# 1bl.net
KiCad netlist of a schematic drawn in EAGLE
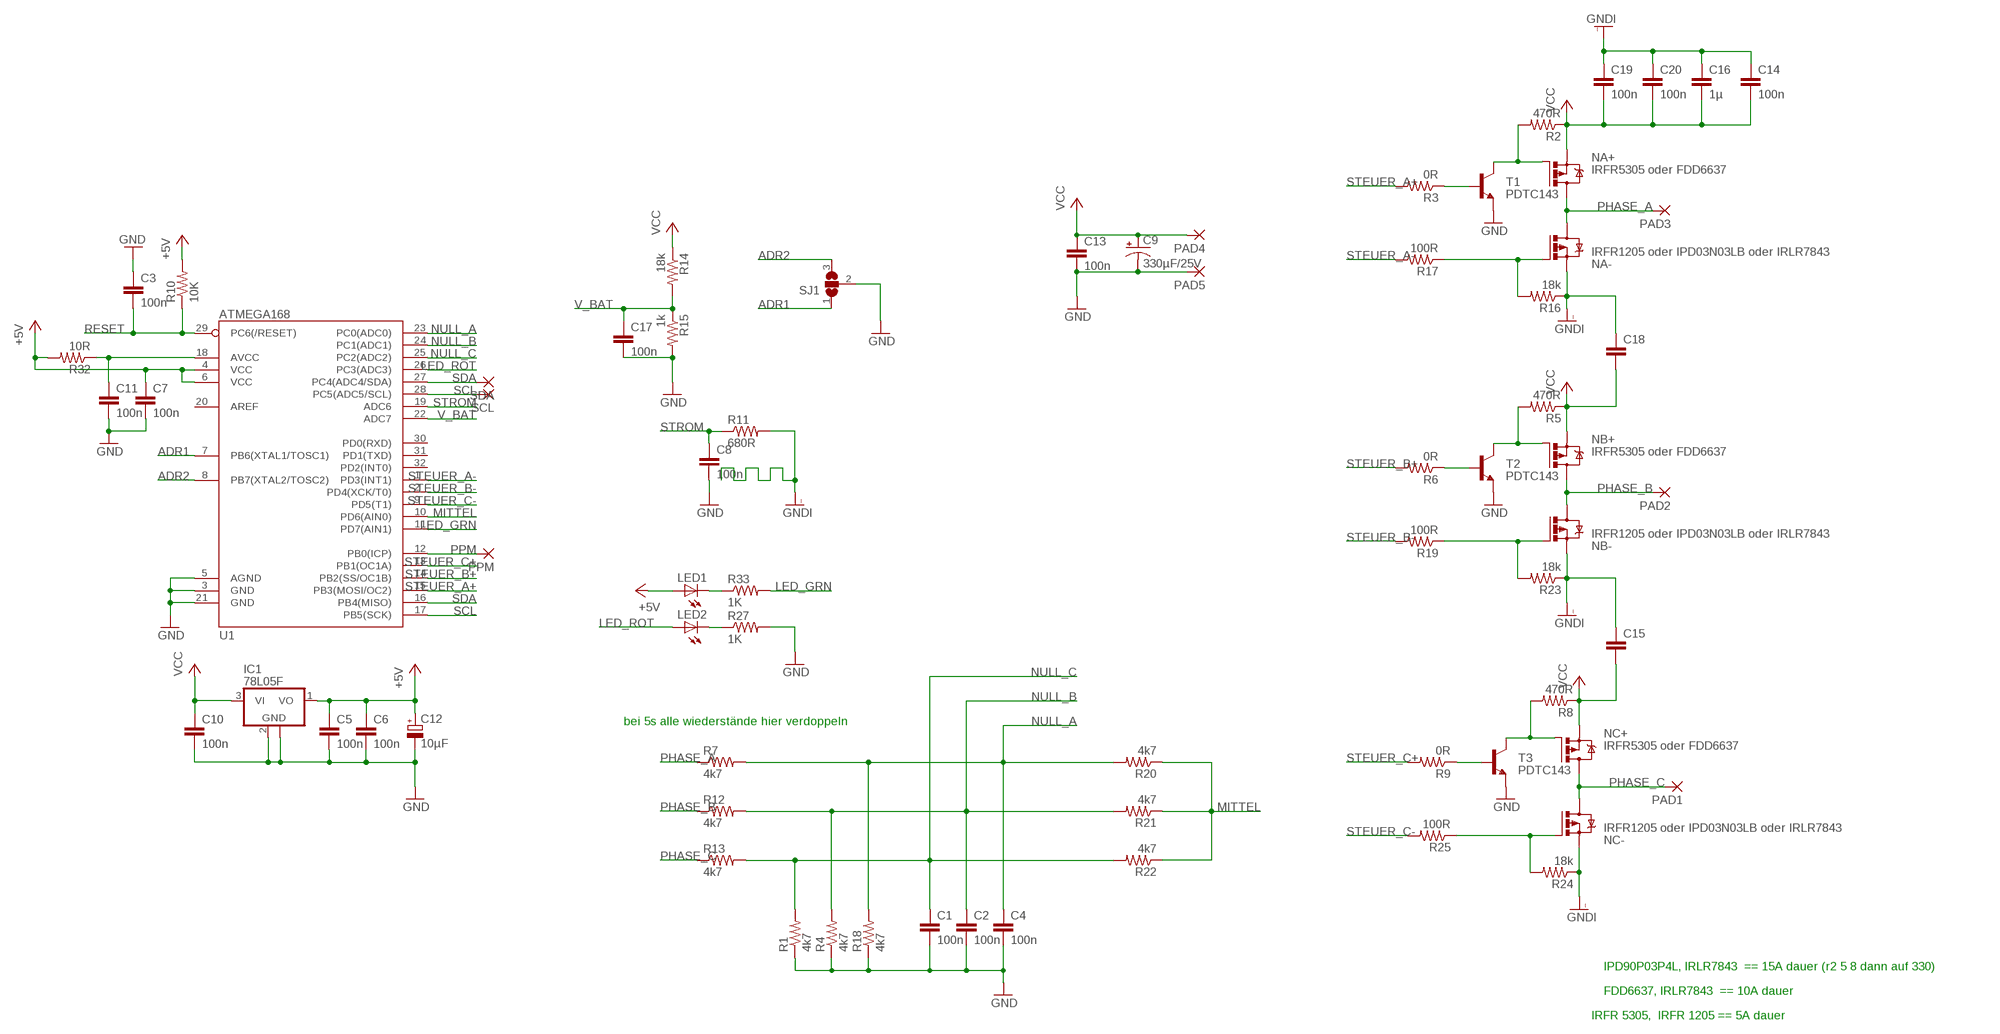
[diagram p0: schematic, sheet 1]

(export (version "E")
  (design (tool "Eeschema 10.0.6"))
  (components
    (comp (ref "C1")
      (value "100n")
      (footprint "eagle-import:0805")
      (libsource (lib "eagle-import") (part "CAP0805"))
    )
    (comp (ref "C2")
      (value "100n")
      (footprint "eagle-import:0805")
      (libsource (lib "eagle-import") (part "CAP0805"))
    )
    (comp (ref "C3")
      (value "100n")
      (footprint "eagle-import:0805")
      (libsource (lib "eagle-import") (part "CAP0805"))
    )
    (comp (ref "C4")
      (value "100n")
      (footprint "eagle-import:0805")
      (libsource (lib "eagle-import") (part "CAP0805"))
    )
    (comp (ref "C5")
      (value "100n")
      (footprint "eagle-import:0805")
      (libsource (lib "eagle-import") (part "CAP0805"))
    )
    (comp (ref "C6")
      (value "100n")
      (footprint "eagle-import:0805")
      (libsource (lib "eagle-import") (part "CAP0805"))
    )
    (comp (ref "C7")
      (value "100n")
      (footprint "eagle-import:0805")
      (libsource (lib "eagle-import") (part "CAP0805"))
    )
    (comp (ref "C8")
      (value "100n")
      (footprint "eagle-import:0805")
      (libsource (lib "eagle-import") (part "CAP0805"))
    )
    (comp (ref "C9")
      (value "330µF/25V")
      (footprint "eagle-import:CPOL-RADIAL-1000UF-25V")
      (libsource (lib "eagle-import") (part "CAP_POLPTH4"))
    )
    (comp (ref "C10")
      (value "100n")
      (footprint "eagle-import:0805")
      (libsource (lib "eagle-import") (part "CAP0805"))
    )
    (comp (ref "C11")
      (value "100n")
      (footprint "eagle-import:0805")
      (libsource (lib "eagle-import") (part "CAP0805"))
    )
    (comp (ref "C12")
      (value "10µF")
      (footprint "eagle-import:PANASONIC_B")
      (libsource (lib "eagle-import") (part "CPOL-EUB"))
    )
    (comp (ref "C13")
      (value "100n")
      (footprint "eagle-import:0805")
      (libsource (lib "eagle-import") (part "CAP0805"))
    )
    (comp (ref "C14")
      (value "100n")
      (footprint "eagle-import:0805")
      (libsource (lib "eagle-import") (part "CAP0805"))
    )
    (comp (ref "C15")
      (value "CAP0805")
      (footprint "eagle-import:0805")
      (libsource (lib "eagle-import") (part "CAP0805"))
    )
    (comp (ref "C16")
      (value "1µ")
      (footprint "eagle-import:0805")
      (libsource (lib "eagle-import") (part "CAP0805"))
    )
    (comp (ref "C17")
      (value "100n")
      (footprint "eagle-import:0805")
      (libsource (lib "eagle-import") (part "CAP0805"))
    )
    (comp (ref "C18")
      (value "CAP0805")
      (footprint "eagle-import:0805")
      (libsource (lib "eagle-import") (part "CAP0805"))
    )
    (comp (ref "C19")
      (value "100n")
      (footprint "eagle-import:0805")
      (libsource (lib "eagle-import") (part "CAP0805"))
    )
    (comp (ref "C20")
      (value "100n")
      (footprint "eagle-import:0805")
      (libsource (lib "eagle-import") (part "CAP0805"))
    )
    (comp (ref "IC1")
      (value "78L05F")
      (footprint "eagle-import:SOT89")
      (libsource (lib "eagle-import") (part "78LF05"))
    )
    (comp (ref "LED1")
      (value "LEDCHIP-LED0805")
      (footprint "eagle-import:CHIP-LED0805")
      (libsource (lib "eagle-import") (part "LEDCHIP-LED0805"))
    )
    (comp (ref "LED2")
      (value "LEDCHIP-LED0805")
      (footprint "eagle-import:CHIP-LED0805")
      (libsource (lib "eagle-import") (part "LEDCHIP-LED0805"))
    )
    (comp (ref "NA+")
      (value "IRFR5305 oder FDD6637")
      (footprint "eagle-import:D-PAK_TO252AA")
      (libsource (lib "eagle-import") (part "IRF?5305R"))
    )
    (comp (ref "NA-")
      (value "IRFR1205 oder IPD03N03LB oder IRLR7843")
      (footprint "eagle-import:D-PAK_TO252AA")
      (libsource (lib "eagle-import") (part "IRF?5305R"))
    )
    (comp (ref "NB+")
      (value "IRFR5305 oder FDD6637")
      (footprint "eagle-import:D-PAK_TO252AA")
      (libsource (lib "eagle-import") (part "IRF?5305R"))
    )
    (comp (ref "NB-")
      (value "IRFR1205 oder IPD03N03LB oder IRLR7843")
      (footprint "eagle-import:D-PAK_TO252AA")
      (libsource (lib "eagle-import") (part "IRF?5305R"))
    )
    (comp (ref "NC+")
      (value "IRFR5305 oder FDD6637")
      (footprint "eagle-import:D-PAK_TO252AA")
      (libsource (lib "eagle-import") (part "IRF?5305R"))
    )
    (comp (ref "NC-")
      (value "IRFR1205 oder IPD03N03LB oder IRLR7843")
      (footprint "eagle-import:D-PAK_TO252AA")
      (libsource (lib "eagle-import") (part "IRF?5305R"))
    )
    (comp (ref "PAD1")
      (value "SMD5")
      (footprint "eagle-import:SMD2,54-5,08")
      (libsource (lib "eagle-import") (part "SMD5"))
    )
    (comp (ref "PAD2")
      (value "SMD5")
      (footprint "eagle-import:SMD2,54-5,08")
      (libsource (lib "eagle-import") (part "SMD5"))
    )
    (comp (ref "PAD3")
      (value "SMD5")
      (footprint "eagle-import:SMD2,54-5,08")
      (libsource (lib "eagle-import") (part "SMD5"))
    )
    (comp (ref "PAD4")
      (value "SMD5")
      (footprint "eagle-import:SMD2,54-5,08")
      (libsource (lib "eagle-import") (part "SMD5"))
    )
    (comp (ref "PAD5")
      (value "SMD5")
      (footprint "eagle-import:SMD2,54-5,08")
      (libsource (lib "eagle-import") (part "SMD5"))
    )
    (comp (ref "PPM")
      (value "SMD2")
      (footprint "eagle-import:SMD1,27-2,54")
      (libsource (lib "eagle-import") (part "SMD2"))
    )
    (comp (ref "R1")
      (value "4k7")
      (footprint "eagle-import:0805")
      (libsource (lib "eagle-import") (part "RESISTOR"))
    )
    (comp (ref "R2")
      (value "470R")
      (footprint "eagle-import:0805")
      (libsource (lib "eagle-import") (part "RESISTOR"))
    )
    (comp (ref "R3")
      (value "0R")
      (footprint "eagle-import:0805")
      (libsource (lib "eagle-import") (part "RESISTOR"))
    )
    (comp (ref "R4")
      (value "4k7")
      (footprint "eagle-import:0805")
      (libsource (lib "eagle-import") (part "RESISTOR"))
    )
    (comp (ref "R5")
      (value "470R")
      (footprint "eagle-import:0805")
      (libsource (lib "eagle-import") (part "RESISTOR"))
    )
    (comp (ref "R6")
      (value "0R")
      (footprint "eagle-import:0805")
      (libsource (lib "eagle-import") (part "RESISTOR"))
    )
    (comp (ref "R7")
      (value "4k7")
      (footprint "eagle-import:0805")
      (libsource (lib "eagle-import") (part "RESISTOR"))
    )
    (comp (ref "R8")
      (value "470R")
      (footprint "eagle-import:0805")
      (libsource (lib "eagle-import") (part "RESISTOR"))
    )
    (comp (ref "R9")
      (value "0R")
      (footprint "eagle-import:0805")
      (libsource (lib "eagle-import") (part "RESISTOR"))
    )
    (comp (ref "R10")
      (value "10K")
      (footprint "eagle-import:0805")
      (libsource (lib "eagle-import") (part "RESISTOR"))
    )
    (comp (ref "R11")
      (value "680R")
      (footprint "eagle-import:0805")
      (libsource (lib "eagle-import") (part "RESISTOR"))
    )
    (comp (ref "R12")
      (value "4k7")
      (footprint "eagle-import:0805")
      (libsource (lib "eagle-import") (part "RESISTOR"))
    )
    (comp (ref "R13")
      (value "4k7")
      (footprint "eagle-import:0805")
      (libsource (lib "eagle-import") (part "RESISTOR"))
    )
    (comp (ref "R14")
      (value "18k")
      (footprint "eagle-import:0805")
      (libsource (lib "eagle-import") (part "RESISTOR"))
    )
    (comp (ref "R15")
      (value "1k")
      (footprint "eagle-import:0805")
      (libsource (lib "eagle-import") (part "RESISTOR"))
    )
    (comp (ref "R16")
      (value "18k")
      (footprint "eagle-import:0805")
      (libsource (lib "eagle-import") (part "RESISTOR"))
    )
    (comp (ref "R17")
      (value "100R")
      (footprint "eagle-import:0805")
      (libsource (lib "eagle-import") (part "RESISTOR"))
    )
    (comp (ref "R18")
      (value "4k7")
      (footprint "eagle-import:0805")
      (libsource (lib "eagle-import") (part "RESISTOR"))
    )
    (comp (ref "R19")
      (value "100R")
      (footprint "eagle-import:0805")
      (libsource (lib "eagle-import") (part "RESISTOR"))
    )
    (comp (ref "R20")
      (value "4k7")
      (footprint "eagle-import:0805")
      (libsource (lib "eagle-import") (part "RESISTOR"))
    )
    (comp (ref "R21")
      (value "4k7")
      (footprint "eagle-import:0805")
      (libsource (lib "eagle-import") (part "RESISTOR"))
    )
    (comp (ref "R22")
      (value "4k7")
      (footprint "eagle-import:0805")
      (libsource (lib "eagle-import") (part "RESISTOR"))
    )
    (comp (ref "R23")
      (value "18k")
      (footprint "eagle-import:0805")
      (libsource (lib "eagle-import") (part "RESISTOR"))
    )
    (comp (ref "R24")
      (value "18k")
      (footprint "eagle-import:0805")
      (libsource (lib "eagle-import") (part "RESISTOR"))
    )
    (comp (ref "R25")
      (value "100R")
      (footprint "eagle-import:0805")
      (libsource (lib "eagle-import") (part "RESISTOR"))
    )
    (comp (ref "R27")
      (value "1K")
      (footprint "eagle-import:0805")
      (libsource (lib "eagle-import") (part "RESISTOR"))
    )
    (comp (ref "R32")
      (value "10R")
      (footprint "eagle-import:0805")
      (libsource (lib "eagle-import") (part "RESISTOR"))
    )
    (comp (ref "R33")
      (value "1K")
      (footprint "eagle-import:0805")
      (libsource (lib "eagle-import") (part "RESISTOR"))
    )
    (comp (ref "SCL")
      (value "SMD2")
      (footprint "eagle-import:SMD1,27-2,54")
      (libsource (lib "eagle-import") (part "SMD2"))
    )
    (comp (ref "SDA")
      (value "SMD2")
      (footprint "eagle-import:SMD1,27-2,54")
      (libsource (lib "eagle-import") (part "SMD2"))
    )
    (comp (ref "SJ1")
      (value "SJ2W")
      (footprint "eagle-import:SJ_2")
      (libsource (lib "eagle-import") (part "SJ2W"))
    )
    (comp (ref "T1")
      (value "PDTC143")
      (footprint "eagle-import:SOT23")
      (libsource (lib "eagle-import") (part "TRANSISTOR_NPNSOT23"))
    )
    (comp (ref "T2")
      (value "PDTC143")
      (footprint "eagle-import:SOT23")
      (libsource (lib "eagle-import") (part "TRANSISTOR_NPNSOT23"))
    )
    (comp (ref "T3")
      (value "PDTC143")
      (footprint "eagle-import:SOT23")
      (libsource (lib "eagle-import") (part "TRANSISTOR_NPNSOT23"))
    )
    (comp (ref "U1")
      (value "ATMEGA168")
      (footprint "eagle-import:TQFP32-08")
      (libsource (lib "eagle-import") (part "ATMEGA168"))
    )
  )
  (nets
    (net (code "1") (name "+5V") (class "Default")
      (node (ref "C12") (pin "+") (pinfunction "+_+") (pintype "passive"))
      (node (ref "C5") (pin "1") (pinfunction "1_1") (pintype "passive"))
      (node (ref "C6") (pin "1") (pinfunction "1_1") (pintype "passive"))
      (node (ref "C7") (pin "1") (pinfunction "1_1") (pintype "passive"))
      (node (ref "IC1") (pin "1") (pinfunction "VO_1") (pintype "passive"))
      (node (ref "LED1") (pin "A") (pinfunction "A_A") (pintype "passive"))
      (node (ref "R10") (pin "2") (pinfunction "2_2") (pintype "passive"))
      (node (ref "R32") (pin "2") (pinfunction "2_2") (pintype "passive"))
      (node (ref "U1") (pin "4") (pinfunction "VCC_4") (pintype "bidirectional"))
      (node (ref "U1") (pin "6") (pinfunction "VCC_6") (pintype "bidirectional"))
    )
    (net (code "2") (name "/ADR1") (class "Default")
      (node (ref "SJ1") (pin "1") (pinfunction "1_1") (pintype "passive"))
      (node (ref "U1") (pin "7") (pinfunction "PB6(XTAL1/TOSC1)_7") (pintype "bidirectional"))
    )
    (net (code "3") (name "/ADR2") (class "Default")
      (node (ref "SJ1") (pin "3") (pinfunction "3_3") (pintype "passive"))
      (node (ref "U1") (pin "8") (pinfunction "PB7(XTAL2/TOSC2)_8") (pintype "bidirectional"))
    )
    (net (code "4") (name "/LED_GRN") (class "Default")
      (node (ref "R33") (pin "2") (pinfunction "2_2") (pintype "passive"))
      (node (ref "U1") (pin "11") (pinfunction "PD7(AIN1)_11") (pintype "bidirectional"))
    )
    (net (code "5") (name "/LED_ROT") (class "Default")
      (node (ref "LED2") (pin "A") (pinfunction "A_A") (pintype "passive"))
      (node (ref "U1") (pin "26") (pinfunction "PC3(ADC3)_26") (pintype "bidirectional"))
    )
    (net (code "6") (name "/MITTEL") (class "Default")
      (node (ref "R20") (pin "1") (pinfunction "1_1") (pintype "passive"))
      (node (ref "R21") (pin "1") (pinfunction "1_1") (pintype "passive"))
      (node (ref "R22") (pin "1") (pinfunction "1_1") (pintype "passive"))
      (node (ref "U1") (pin "10") (pinfunction "PD6(AIN0)_10") (pintype "bidirectional"))
    )
    (net (code "7") (name "/NULL_A") (class "Default")
      (node (ref "C4") (pin "1") (pinfunction "1_1") (pintype "passive"))
      (node (ref "R18") (pin "2") (pinfunction "2_2") (pintype "passive"))
      (node (ref "R20") (pin "2") (pinfunction "2_2") (pintype "passive"))
      (node (ref "R7") (pin "2") (pinfunction "2_2") (pintype "passive"))
      (node (ref "U1") (pin "23") (pinfunction "PC0(ADC0)_23") (pintype "bidirectional"))
    )
    (net (code "8") (name "/NULL_B") (class "Default")
      (node (ref "C2") (pin "1") (pinfunction "1_1") (pintype "passive"))
      (node (ref "R12") (pin "2") (pinfunction "2_2") (pintype "passive"))
      (node (ref "R21") (pin "2") (pinfunction "2_2") (pintype "passive"))
      (node (ref "R4") (pin "2") (pinfunction "2_2") (pintype "passive"))
      (node (ref "U1") (pin "24") (pinfunction "PC1(ADC1)_24") (pintype "bidirectional"))
    )
    (net (code "9") (name "/NULL_C") (class "Default")
      (node (ref "C1") (pin "1") (pinfunction "1_1") (pintype "passive"))
      (node (ref "R1") (pin "2") (pinfunction "2_2") (pintype "passive"))
      (node (ref "R13") (pin "2") (pinfunction "2_2") (pintype "passive"))
      (node (ref "R22") (pin "2") (pinfunction "2_2") (pintype "passive"))
      (node (ref "U1") (pin "25") (pinfunction "PC2(ADC2)_25") (pintype "bidirectional"))
    )
    (net (code "10") (name "/PHASE_A") (class "Default")
      (node (ref "NA+") (pin "4") (pinfunction "D_4") (pintype "passive"))
      (node (ref "NA-") (pin "4") (pinfunction "D_4") (pintype "passive"))
      (node (ref "PAD3") (pin "1") (pinfunction "P_1") (pintype "passive"))
      (node (ref "R7") (pin "1") (pinfunction "1_1") (pintype "passive"))
    )
    (net (code "11") (name "/PHASE_B") (class "Default")
      (node (ref "NB+") (pin "4") (pinfunction "D_4") (pintype "passive"))
      (node (ref "NB-") (pin "4") (pinfunction "D_4") (pintype "passive"))
      (node (ref "PAD2") (pin "1") (pinfunction "P_1") (pintype "passive"))
      (node (ref "R12") (pin "1") (pinfunction "1_1") (pintype "passive"))
    )
    (net (code "12") (name "/PHASE_C") (class "Default")
      (node (ref "NC+") (pin "4") (pinfunction "D_4") (pintype "passive"))
      (node (ref "NC-") (pin "4") (pinfunction "D_4") (pintype "passive"))
      (node (ref "PAD1") (pin "1") (pinfunction "P_1") (pintype "passive"))
      (node (ref "R13") (pin "1") (pinfunction "1_1") (pintype "passive"))
    )
    (net (code "13") (name "/PPM") (class "Default")
      (node (ref "PPM") (pin "1") (pinfunction "P_1") (pintype "passive"))
      (node (ref "U1") (pin "12") (pinfunction "PB0(ICP)_12") (pintype "bidirectional"))
    )
    (net (code "14") (name "/RESET") (class "Default")
      (node (ref "C3") (pin "2") (pinfunction "2_2") (pintype "passive"))
      (node (ref "R10") (pin "1") (pinfunction "1_1") (pintype "passive"))
      (node (ref "U1") (pin "29") (pinfunction "PC6(/RESET)_29") (pintype "bidirectional"))
    )
    (net (code "15") (name "/SCL") (class "Default")
      (node (ref "SCL") (pin "1") (pinfunction "P_1") (pintype "passive"))
      (node (ref "U1") (pin "17") (pinfunction "PB5(SCK)_17") (pintype "bidirectional"))
      (node (ref "U1") (pin "28") (pinfunction "PC5(ADC5/SCL)_28") (pintype "bidirectional"))
    )
    (net (code "16") (name "/SDA") (class "Default")
      (node (ref "SDA") (pin "1") (pinfunction "P_1") (pintype "passive"))
      (node (ref "U1") (pin "16") (pinfunction "PB4(MISO)_16") (pintype "bidirectional"))
      (node (ref "U1") (pin "27") (pinfunction "PC4(ADC4/SDA)_27") (pintype "bidirectional"))
    )
    (net (code "17") (name "/STEUER_A+") (class "Default")
      (node (ref "R3") (pin "2") (pinfunction "2_2") (pintype "passive"))
      (node (ref "U1") (pin "15") (pinfunction "PB3(MOSI/OC2)_15") (pintype "bidirectional"))
    )
    (net (code "18") (name "/STEUER_A-") (class "Default")
      (node (ref "R17") (pin "2") (pinfunction "2_2") (pintype "passive"))
      (node (ref "U1") (pin "1") (pinfunction "PD3(INT1)_1") (pintype "bidirectional"))
    )
    (net (code "19") (name "/STEUER_B+") (class "Default")
      (node (ref "R6") (pin "2") (pinfunction "2_2") (pintype "passive"))
      (node (ref "U1") (pin "14") (pinfunction "PB2(SS/OC1B)_14") (pintype "bidirectional"))
    )
    (net (code "20") (name "/STEUER_B-") (class "Default")
      (node (ref "R19") (pin "2") (pinfunction "2_2") (pintype "passive"))
      (node (ref "U1") (pin "2") (pinfunction "PD4(XCK/T0)_2") (pintype "bidirectional"))
    )
    (net (code "21") (name "/STEUER_C+") (class "Default")
      (node (ref "R9") (pin "2") (pinfunction "2_2") (pintype "passive"))
      (node (ref "U1") (pin "13") (pinfunction "PB1(OC1A)_13") (pintype "bidirectional"))
    )
    (net (code "22") (name "/STEUER_C-") (class "Default")
      (node (ref "R25") (pin "2") (pinfunction "2_2") (pintype "passive"))
      (node (ref "U1") (pin "9") (pinfunction "PD5(T1)_9") (pintype "bidirectional"))
    )
    (net (code "23") (name "/STROM") (class "Default")
      (node (ref "C8") (pin "1") (pinfunction "1_1") (pintype "passive"))
      (node (ref "R11") (pin "1") (pinfunction "1_1") (pintype "passive"))
      (node (ref "U1") (pin "19") (pinfunction "ADC6_19") (pintype "bidirectional"))
    )
    (net (code "24") (name "/V_BAT") (class "Default")
      (node (ref "C17") (pin "1") (pinfunction "1_1") (pintype "passive"))
      (node (ref "R14") (pin "2") (pinfunction "2_2") (pintype "passive"))
      (node (ref "R15") (pin "1") (pinfunction "1_1") (pintype "passive"))
      (node (ref "U1") (pin "22") (pinfunction "ADC7_22") (pintype "bidirectional"))
    )
    (net (code "25") (name "GND") (class "Default")
      (node (ref "C1") (pin "2") (pinfunction "2_2") (pintype "passive"))
      (node (ref "C10") (pin "2") (pinfunction "2_2") (pintype "passive"))
      (node (ref "C11") (pin "2") (pinfunction "2_2") (pintype "passive"))
      (node (ref "C12") (pin "-") (pinfunction "-_-") (pintype "passive"))
      (node (ref "C13") (pin "2") (pinfunction "2_2") (pintype "passive"))
      (node (ref "C17") (pin "2") (pinfunction "2_2") (pintype "passive"))
      (node (ref "C2") (pin "2") (pinfunction "2_2") (pintype "passive"))
      (node (ref "C3") (pin "1") (pinfunction "1_1") (pintype "passive"))
      (node (ref "C4") (pin "2") (pinfunction "2_2") (pintype "passive"))
      (node (ref "C5") (pin "2") (pinfunction "2_2") (pintype "passive"))
      (node (ref "C6") (pin "2") (pinfunction "2_2") (pintype "passive"))
      (node (ref "C7") (pin "2") (pinfunction "2_2") (pintype "passive"))
      (node (ref "C8") (pin "2") (pinfunction "2_2") (pintype "passive"))
      (node (ref "C9") (pin "2") (pinfunction "-_2") (pintype "passive"))
      (node (ref "IC1") (pin "2") (pinfunction "GND_2") (pintype "passive"))
      (node (ref "IC1") (pin "2@1") (pinfunction "GND_2@1") (pintype "passive"))
      (node (ref "PAD5") (pin "1") (pinfunction "P_1") (pintype "passive"))
      (node (ref "R1") (pin "1") (pinfunction "1_1") (pintype "passive"))
      (node (ref "R15") (pin "2") (pinfunction "2_2") (pintype "passive"))
      (node (ref "R18") (pin "1") (pinfunction "1_1") (pintype "passive"))
      (node (ref "R27") (pin "2") (pinfunction "2_2") (pintype "passive"))
      (node (ref "R4") (pin "1") (pinfunction "1_1") (pintype "passive"))
      (node (ref "SJ1") (pin "2") (pinfunction "2_2") (pintype "passive"))
      (node (ref "T1") (pin "2") (pinfunction "E_2") (pintype "passive"))
      (node (ref "T2") (pin "2") (pinfunction "E_2") (pintype "passive"))
      (node (ref "T3") (pin "2") (pinfunction "E_2") (pintype "passive"))
      (node (ref "U1") (pin "21") (pinfunction "GND_21") (pintype "bidirectional"))
      (node (ref "U1") (pin "3") (pinfunction "GND_3") (pintype "bidirectional"))
      (node (ref "U1") (pin "5") (pinfunction "AGND_5") (pintype "bidirectional"))
    )
    (net (code "26") (name "GNDI") (class "Default")
      (node (ref "C14") (pin "1") (pinfunction "1_1") (pintype "passive"))
      (node (ref "C15") (pin "1") (pinfunction "1_1") (pintype "passive"))
      (node (ref "C16") (pin "1") (pinfunction "1_1") (pintype "passive"))
      (node (ref "C18") (pin "1") (pinfunction "1_1") (pintype "passive"))
      (node (ref "C19") (pin "1") (pinfunction "1_1") (pintype "passive"))
      (node (ref "C20") (pin "1") (pinfunction "1_1") (pintype "passive"))
      (node (ref "NA-") (pin "3") (pinfunction "S_3") (pintype "passive"))
      (node (ref "NB-") (pin "3") (pinfunction "S_3") (pintype "passive"))
      (node (ref "NC-") (pin "3") (pinfunction "S_3") (pintype "passive"))
      (node (ref "R11") (pin "2") (pinfunction "2_2") (pintype "passive"))
      (node (ref "R16") (pin "1") (pinfunction "1_1") (pintype "passive"))
      (node (ref "R23") (pin "1") (pinfunction "1_1") (pintype "passive"))
      (node (ref "R24") (pin "1") (pinfunction "1_1") (pintype "passive"))
    )
    (net (code "27") (name "Net-(LED1-PadC)") (class "Default")
      (node (ref "LED1") (pin "C") (pinfunction "C_C") (pintype "passive"))
      (node (ref "R33") (pin "1") (pinfunction "1_1") (pintype "passive"))
    )
    (net (code "28") (name "Net-(LED2-PadC)") (class "Default")
      (node (ref "LED2") (pin "C") (pinfunction "C_C") (pintype "passive"))
      (node (ref "R27") (pin "1") (pinfunction "1_1") (pintype "passive"))
    )
    (net (code "29") (name "Net-(NA+-G)") (class "Default")
      (node (ref "NA+") (pin "1") (pinfunction "G_1") (pintype "passive"))
      (node (ref "R2") (pin "2") (pinfunction "2_2") (pintype "passive"))
      (node (ref "T1") (pin "3") (pinfunction "C_3") (pintype "passive"))
    )
    (net (code "30") (name "Net-(NA--G)") (class "Default")
      (node (ref "NA-") (pin "1") (pinfunction "G_1") (pintype "passive"))
      (node (ref "R16") (pin "2") (pinfunction "2_2") (pintype "passive"))
      (node (ref "R17") (pin "1") (pinfunction "1_1") (pintype "passive"))
    )
    (net (code "31") (name "Net-(NB+-G)") (class "Default")
      (node (ref "NB+") (pin "1") (pinfunction "G_1") (pintype "passive"))
      (node (ref "R5") (pin "2") (pinfunction "2_2") (pintype "passive"))
      (node (ref "T2") (pin "3") (pinfunction "C_3") (pintype "passive"))
    )
    (net (code "32") (name "Net-(NB--G)") (class "Default")
      (node (ref "NB-") (pin "1") (pinfunction "G_1") (pintype "passive"))
      (node (ref "R19") (pin "1") (pinfunction "1_1") (pintype "passive"))
      (node (ref "R23") (pin "2") (pinfunction "2_2") (pintype "passive"))
    )
    (net (code "33") (name "Net-(NC+-G)") (class "Default")
      (node (ref "NC+") (pin "1") (pinfunction "G_1") (pintype "passive"))
      (node (ref "R8") (pin "2") (pinfunction "2_2") (pintype "passive"))
      (node (ref "T3") (pin "3") (pinfunction "C_3") (pintype "passive"))
    )
    (net (code "34") (name "Net-(NC--G)") (class "Default")
      (node (ref "NC-") (pin "1") (pinfunction "G_1") (pintype "passive"))
      (node (ref "R24") (pin "2") (pinfunction "2_2") (pintype "passive"))
      (node (ref "R25") (pin "1") (pinfunction "1_1") (pintype "passive"))
    )
    (net (code "35") (name "Net-(T1-B)") (class "Default")
      (node (ref "R3") (pin "1") (pinfunction "1_1") (pintype "passive"))
      (node (ref "T1") (pin "1") (pinfunction "B_1") (pintype "passive"))
    )
    (net (code "36") (name "Net-(T2-B)") (class "Default")
      (node (ref "R6") (pin "1") (pinfunction "1_1") (pintype "passive"))
      (node (ref "T2") (pin "1") (pinfunction "B_1") (pintype "passive"))
    )
    (net (code "37") (name "Net-(T3-B)") (class "Default")
      (node (ref "R9") (pin "1") (pinfunction "1_1") (pintype "passive"))
      (node (ref "T3") (pin "1") (pinfunction "B_1") (pintype "passive"))
    )
    (net (code "38") (name "Net-(U1-AVCC)") (class "Default")
      (node (ref "C11") (pin "1") (pinfunction "1_1") (pintype "passive"))
      (node (ref "R32") (pin "1") (pinfunction "1_1") (pintype "passive"))
      (node (ref "U1") (pin "18") (pinfunction "AVCC_18") (pintype "bidirectional"))
    )
    (net (code "39") (name "VCC") (class "Default")
      (node (ref "C10") (pin "1") (pinfunction "1_1") (pintype "passive"))
      (node (ref "C13") (pin "1") (pinfunction "1_1") (pintype "passive"))
      (node (ref "C14") (pin "2") (pinfunction "2_2") (pintype "passive"))
      (node (ref "C15") (pin "2") (pinfunction "2_2") (pintype "passive"))
      (node (ref "C16") (pin "2") (pinfunction "2_2") (pintype "passive"))
      (node (ref "C18") (pin "2") (pinfunction "2_2") (pintype "passive"))
      (node (ref "C19") (pin "2") (pinfunction "2_2") (pintype "passive"))
      (node (ref "C20") (pin "2") (pinfunction "2_2") (pintype "passive"))
      (node (ref "C9") (pin "1") (pinfunction "+_1") (pintype "passive"))
      (node (ref "IC1") (pin "3") (pinfunction "VI_3") (pintype "input"))
      (node (ref "NA+") (pin "3") (pinfunction "S_3") (pintype "passive"))
      (node (ref "NB+") (pin "3") (pinfunction "S_3") (pintype "passive"))
      (node (ref "NC+") (pin "3") (pinfunction "S_3") (pintype "passive"))
      (node (ref "PAD4") (pin "1") (pinfunction "P_1") (pintype "passive"))
      (node (ref "R14") (pin "1") (pinfunction "1_1") (pintype "passive"))
      (node (ref "R2") (pin "1") (pinfunction "1_1") (pintype "passive"))
      (node (ref "R5") (pin "1") (pinfunction "1_1") (pintype "passive"))
      (node (ref "R8") (pin "1") (pinfunction "1_1") (pintype "passive"))
    )
    (net (code "40") (name "unconnected-(U1-AREF-Pad20)") (class "Default")
      (node (ref "U1") (pin "20") (pinfunction "AREF_20") (pintype "bidirectional"))
    )
    (net (code "41") (name "unconnected-(U1-PD0(RXD)-Pad30)") (class "Default")
      (node (ref "U1") (pin "30") (pinfunction "PD0(RXD)_30") (pintype "bidirectional"))
    )
    (net (code "42") (name "unconnected-(U1-PD1(TXD)-Pad31)") (class "Default")
      (node (ref "U1") (pin "31") (pinfunction "PD1(TXD)_31") (pintype "bidirectional"))
    )
    (net (code "43") (name "unconnected-(U1-PD2(INT0)-Pad32)") (class "Default")
      (node (ref "U1") (pin "32") (pinfunction "PD2(INT0)_32") (pintype "bidirectional"))
    )
  )
)
